# ProPrj_Mach_Card_2026-06-03.net
KiCad netlist of a schematic drawn in EasyEDA Pro
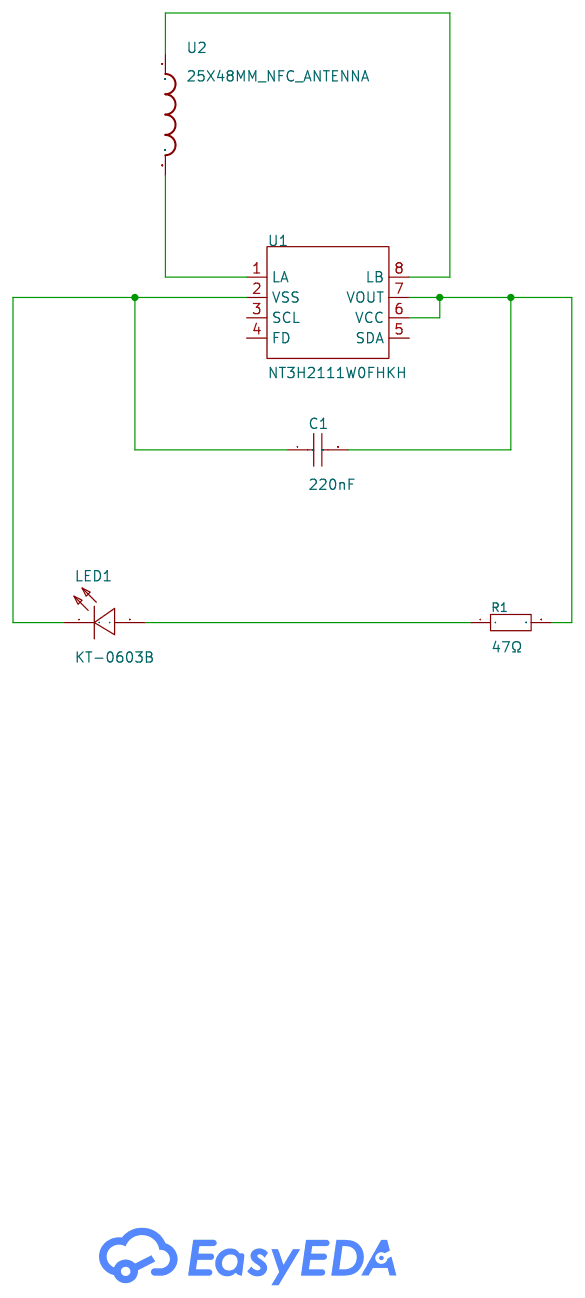
[diagram p0: schematic sheet]

(export (version "E")
  (design (tool "Eeschema 10.0.6"))
  (components
    (comp (ref "C1")
      (value "220nF")
      (footprint "easyedapro:C0603")
      (description "Capacitance:220nF Tolerance:±10% Tolerance:±10% Voltage Rating:25V Temperature Coefficient:X7R")
      (fields
        (field (name "Manufacturer Part") "CL10B224KA8NNNC")
        (field (name "Manufacturer") "SAMSUNG(三星)")
      )
      (libsource (lib "easyedapro") (part "CL10B224KA8NNNC"))
    )
    (comp (ref "LED1")
      (value "KT-0603B")
      (footprint "easyedapro:LED0603-RD")
      (fields (field (name "Manufacturer") "KENTO"))
      (libsource (lib "easyedapro") (part "Blue light 0603"))
    )
    (comp (ref "R1")
      (value "47Ω")
      (footprint "easyedapro:R0603")
      (fields
        (field (name "Manufacturer Part") "0603WAF470JT5E")
        (field (name "Manufacturer") "UNI-ROYAL(厚声)")
      )
      (libsource (lib "easyedapro") (part "0603WAF470JT5E"))
    )
    (comp (ref "U1")
      (value "NT3H2111W0FHKH")
      (footprint "easyedapro:XQFN-8_L1.6-W1.6-P0.50-BL_NT3H2111W0FHKH")
      (fields (field (name "Manufacturer") "NXP(恩智浦)"))
      (libsource (lib "easyedapro") (part "NT3H2111W0FHKH"))
    )
    (comp (ref "U2")
      (value "25X48MM_NFC_ANTENNA")
      (footprint "easyedapro:25X48MM_NFC_ANTENNA")
      (libsource (lib "easyedapro") (part "25X48MM_NFC_ANTENNA"))
    )
  )
  (nets
    (net (code "1") (name "Net-(LED1-A)") (class "Default")
      (node (ref "LED1") (pin "2") (pinfunction "A_2") (pintype "unspecified"))
      (node (ref "R1") (pin "1") (pinfunction "1_1") (pintype "input"))
    )
    (net (code "2") (name "Net-(LED1-K)") (class "Default")
      (node (ref "C1") (pin "1") (pinfunction "1_1") (pintype "input"))
      (node (ref "LED1") (pin "1") (pinfunction "K_1") (pintype "unspecified"))
      (node (ref "U1") (pin "2") (pinfunction "VSS_2") (pintype "unspecified"))
    )
    (net (code "3") (name "Net-(U1-LA)") (class "Default")
      (node (ref "U1") (pin "1") (pinfunction "LA_1") (pintype "unspecified"))
      (node (ref "U2") (pin "P$2") (pinfunction "P$2_P$2") (pintype "bidirectional"))
    )
    (net (code "4") (name "Net-(U1-LB)") (class "Default")
      (node (ref "U1") (pin "8") (pinfunction "LB_8") (pintype "unspecified"))
      (node (ref "U2") (pin "P$1") (pinfunction "P$1_P$1") (pintype "bidirectional"))
    )
    (net (code "5") (name "Net-(U1-VCC)") (class "Default")
      (node (ref "C1") (pin "2") (pinfunction "2_2") (pintype "input"))
      (node (ref "R1") (pin "2") (pinfunction "2_2") (pintype "input"))
      (node (ref "U1") (pin "6") (pinfunction "VCC_6") (pintype "unspecified"))
      (node (ref "U1") (pin "7") (pinfunction "VOUT_7") (pintype "unspecified"))
    )
    (net (code "6") (name "unconnected-(U1-FD-Pad4)") (class "Default")
      (node (ref "U1") (pin "4") (pinfunction "FD_4") (pintype "unspecified"))
    )
    (net (code "7") (name "unconnected-(U1-SCL-Pad3)") (class "Default")
      (node (ref "U1") (pin "3") (pinfunction "SCL_3") (pintype "unspecified"))
    )
    (net (code "8") (name "unconnected-(U1-SDA-Pad5)") (class "Default")
      (node (ref "U1") (pin "5") (pinfunction "SDA_5") (pintype "unspecified"))
    )
  )
)
